# Joystick.net
KiCad netlist of a schematic drawn in Altium Designer
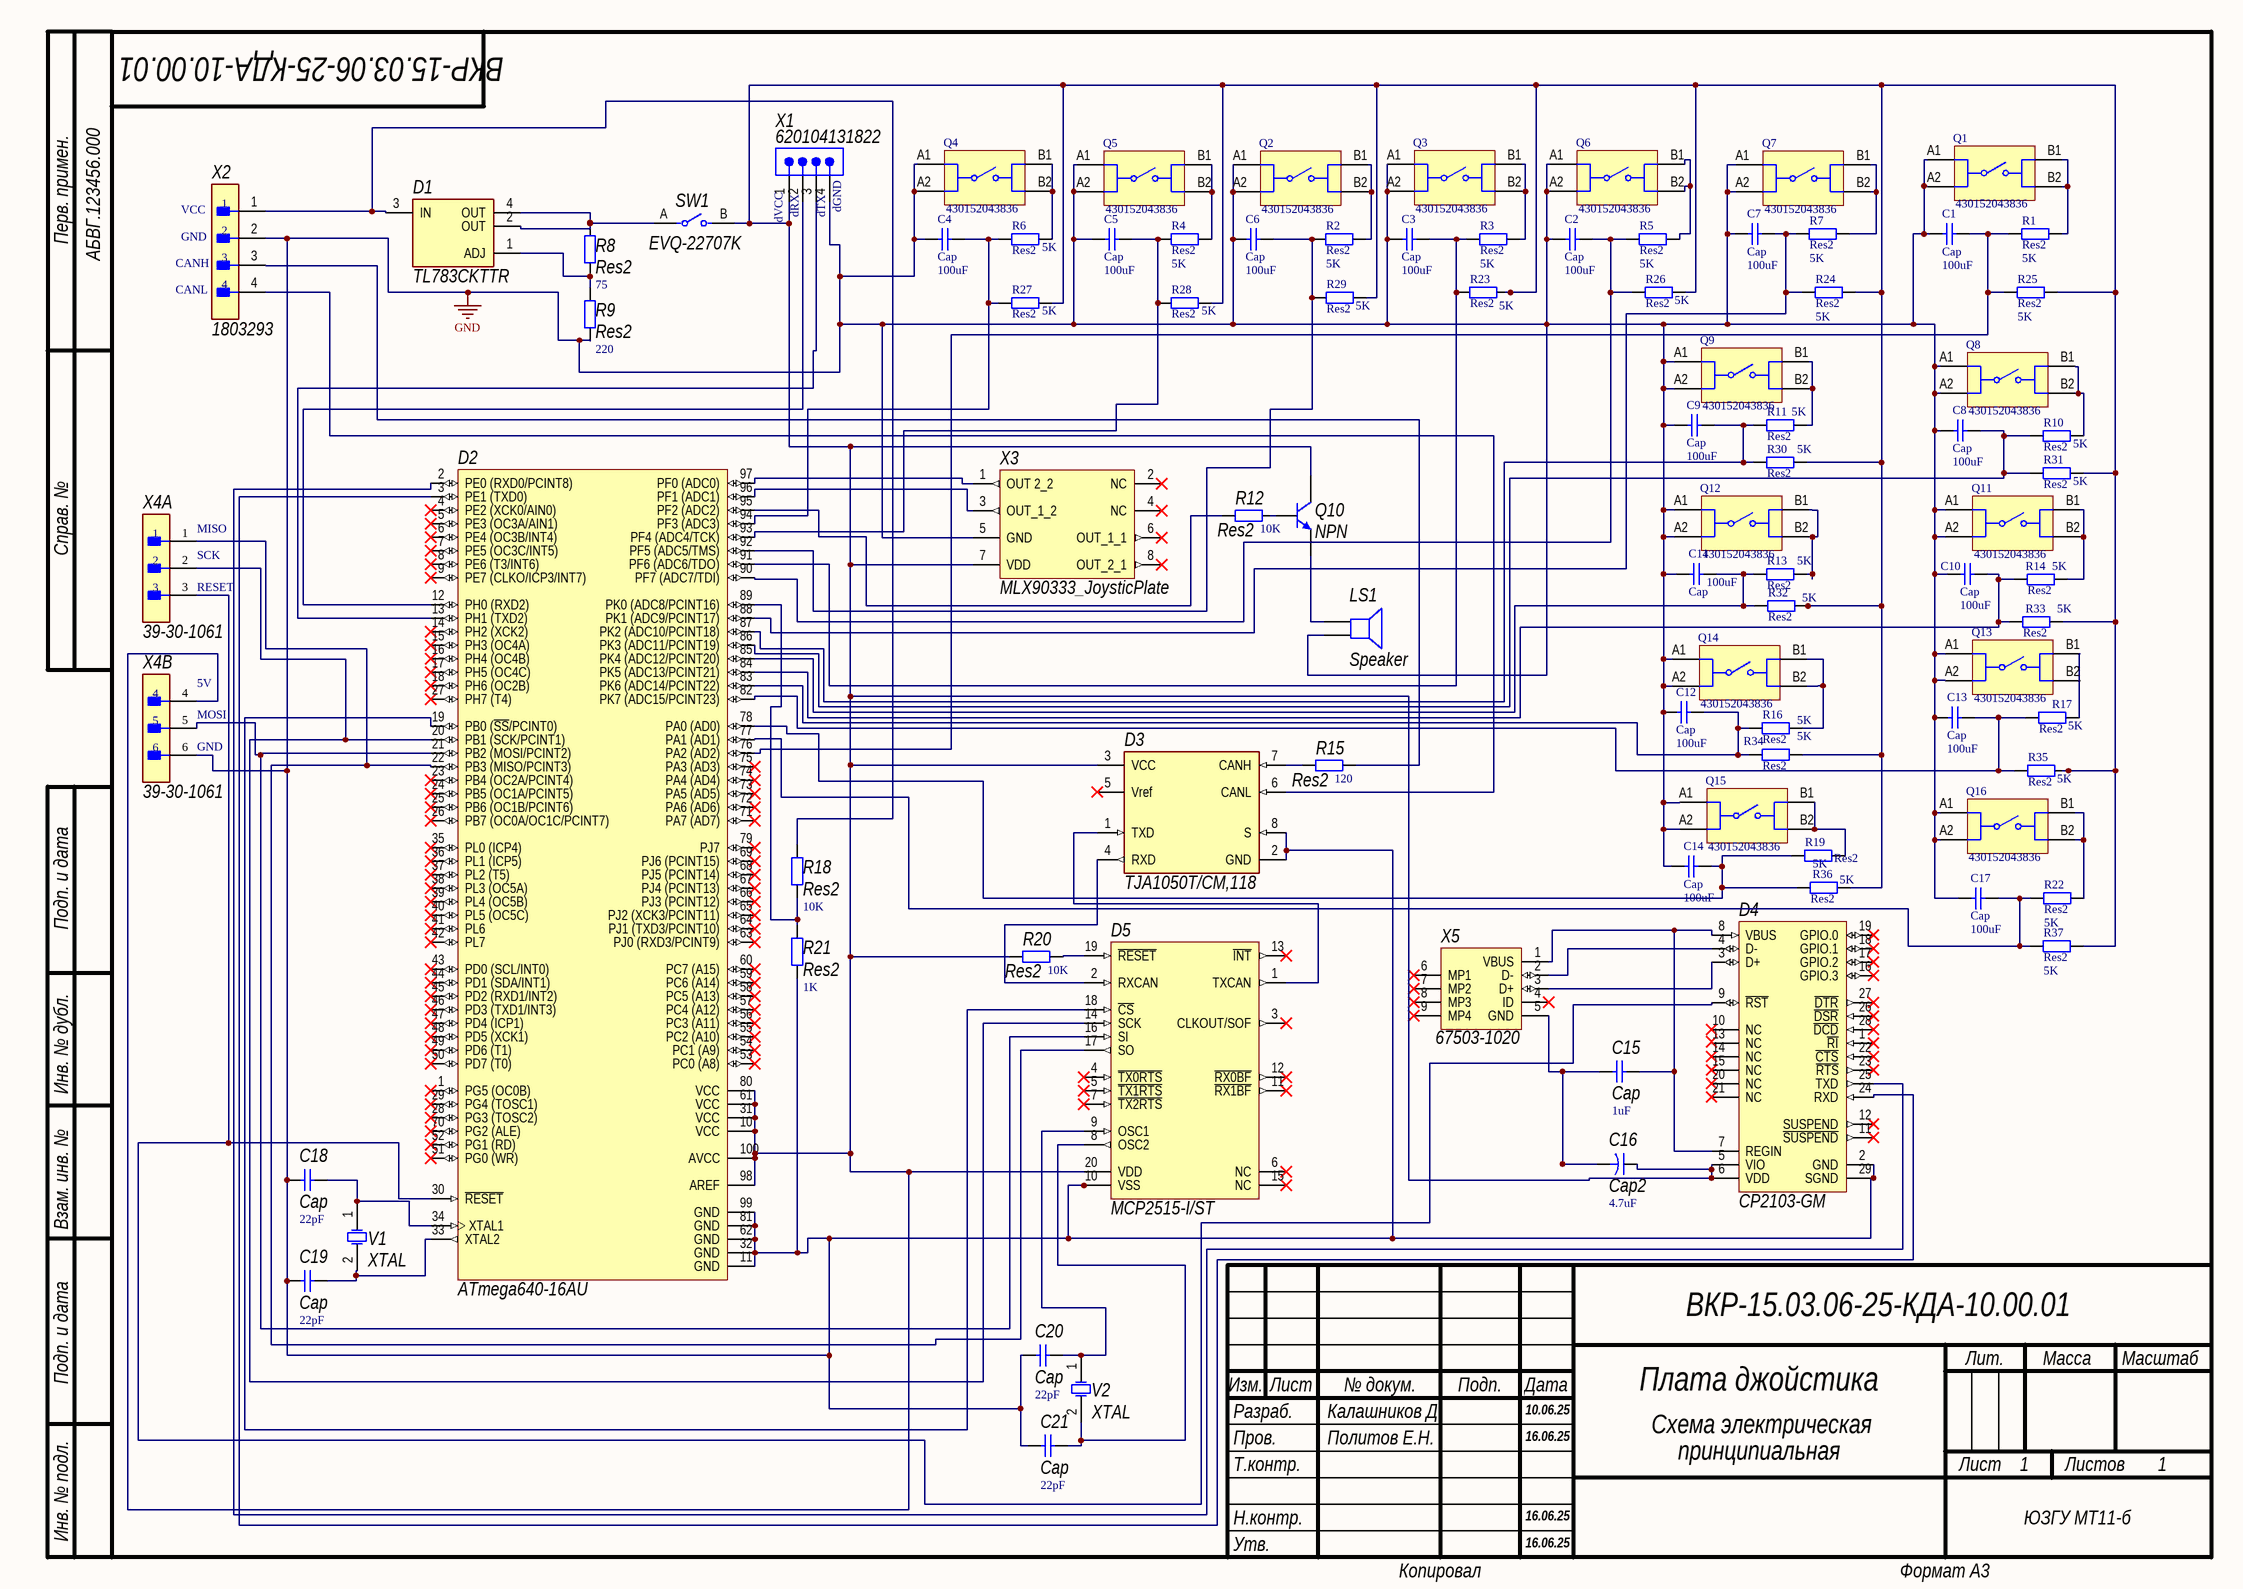
[diagram p0: Joystick.SchDoc]

(export (version "E")
  (design (tool "Eeschema 10.0.6"))
  (components
    (comp (ref "C1")
      (value "Cap")
      (footprint "RAD-0.3")
      (description "Capacitor")
      (fields (field (name "ALTIUM_VALUE") "100uF") (field (name "PUBLISHER") "Altium Limited"))
      (libsource (lib "Miscellaneous Devices") (part "Cap"))
    )
    (comp (ref "C2")
      (value "Cap")
      (footprint "RAD-0.3")
      (description "Capacitor")
      (fields (field (name "ALTIUM_VALUE") "100uF") (field (name "PUBLISHER") "Altium Limited"))
      (libsource (lib "Miscellaneous Devices") (part "Cap"))
    )
    (comp (ref "C3")
      (value "Cap")
      (footprint "RAD-0.3")
      (description "Capacitor")
      (fields (field (name "ALTIUM_VALUE") "100uF") (field (name "PUBLISHER") "Altium Limited"))
      (libsource (lib "Miscellaneous Devices") (part "Cap"))
    )
    (comp (ref "C4")
      (value "Cap")
      (footprint "RAD-0.3")
      (description "Capacitor")
      (fields (field (name "ALTIUM_VALUE") "100uF") (field (name "PUBLISHER") "Altium Limited"))
      (libsource (lib "Miscellaneous Devices") (part "Cap"))
    )
    (comp (ref "C5")
      (value "Cap")
      (footprint "RAD-0.3")
      (description "Capacitor")
      (fields (field (name "ALTIUM_VALUE") "100uF") (field (name "PUBLISHER") "Altium Limited"))
      (libsource (lib "Miscellaneous Devices") (part "Cap"))
    )
    (comp (ref "C6")
      (value "Cap")
      (footprint "RAD-0.3")
      (description "Capacitor")
      (fields (field (name "ALTIUM_VALUE") "100uF") (field (name "PUBLISHER") "Altium Limited"))
      (libsource (lib "Miscellaneous Devices") (part "Cap"))
    )
    (comp (ref "C7")
      (value "Cap")
      (footprint "RAD-0.3")
      (description "Capacitor")
      (fields (field (name "ALTIUM_VALUE") "100uF") (field (name "PUBLISHER") "Altium Limited"))
      (libsource (lib "Miscellaneous Devices") (part "Cap"))
    )
    (comp (ref "C8")
      (value "Cap")
      (footprint "RAD-0.3")
      (description "Capacitor")
      (fields (field (name "ALTIUM_VALUE") "100uF") (field (name "PUBLISHER") "Altium Limited"))
      (libsource (lib "Miscellaneous Devices") (part "Cap"))
    )
    (comp (ref "C9")
      (value "Cap")
      (footprint "RAD-0.3")
      (description "Capacitor")
      (fields (field (name "ALTIUM_VALUE") "100uF") (field (name "PUBLISHER") "Altium Limited"))
      (libsource (lib "Miscellaneous Devices") (part "Cap"))
    )
    (comp (ref "C10")
      (value "Cap")
      (footprint "RAD-0.3")
      (description "Capacitor")
      (fields (field (name "ALTIUM_VALUE") "100uF") (field (name "PUBLISHER") "Altium Limited"))
      (libsource (lib "Miscellaneous Devices") (part "Cap"))
    )
    (comp (ref "C11")
      (value "Cap")
      (footprint "RAD-0.3")
      (description "Capacitor")
      (fields (field (name "ALTIUM_VALUE") "100uF") (field (name "PUBLISHER") "Altium Limited"))
      (libsource (lib "Miscellaneous Devices") (part "Cap"))
    )
    (comp (ref "C12")
      (value "Cap")
      (footprint "RAD-0.3")
      (description "Capacitor")
      (fields (field (name "ALTIUM_VALUE") "100uF") (field (name "PUBLISHER") "Altium Limited"))
      (libsource (lib "Miscellaneous Devices") (part "Cap"))
    )
    (comp (ref "C13")
      (value "Cap")
      (footprint "RAD-0.3")
      (description "Capacitor")
      (fields (field (name "ALTIUM_VALUE") "100uF") (field (name "PUBLISHER") "Altium Limited"))
      (libsource (lib "Miscellaneous Devices") (part "Cap"))
    )
    (comp (ref "C14")
      (value "Cap")
      (footprint "RAD-0.3")
      (description "Capacitor")
      (fields (field (name "ALTIUM_VALUE") "100uF") (field (name "PUBLISHER") "Altium Limited"))
      (libsource (lib "Miscellaneous Devices") (part "Cap"))
    )
    (comp (ref "C15")
      (value "Cap")
      (footprint "RAD-0.3")
      (description "Capacitor")
      (fields (field (name "ALTIUM_VALUE") "1uF") (field (name "PUBLISHER") "Altium Limited"))
      (libsource (lib "Miscellaneous Devices") (part "Cap"))
    )
    (comp (ref "C16")
      (value "Cap2")
      (footprint "CAPR5-4X5")
      (description "Capacitor")
      (fields (field (name "ALTIUM_VALUE") "4.7uF") (field (name "PUBLISHER") "Altium Limited"))
      (libsource (lib "Miscellaneous Devices") (part "Cap2"))
    )
    (comp (ref "C17")
      (value "Cap")
      (footprint "RAD-0.3")
      (description "Capacitor")
      (fields (field (name "ALTIUM_VALUE") "100uF") (field (name "PUBLISHER") "Altium Limited"))
      (libsource (lib "Miscellaneous Devices") (part "Cap"))
    )
    (comp (ref "C18")
      (value "Cap")
      (footprint "RAD-0.3")
      (description "Capacitor")
      (fields (field (name "ALTIUM_VALUE") "22pF") (field (name "PUBLISHER") "Altium Limited"))
      (libsource (lib "Miscellaneous Devices") (part "Cap"))
    )
    (comp (ref "C19")
      (value "Cap")
      (footprint "RAD-0.3")
      (description "Capacitor")
      (fields (field (name "ALTIUM_VALUE") "22pF") (field (name "PUBLISHER") "Altium Limited"))
      (libsource (lib "Miscellaneous Devices") (part "Cap"))
    )
    (comp (ref "C20")
      (value "Cap")
      (footprint "RAD-0.3")
      (description "Capacitor")
      (fields (field (name "ALTIUM_VALUE") "22pF") (field (name "PUBLISHER") "Altium Limited"))
      (libsource (lib "Miscellaneous Devices") (part "Cap"))
    )
    (comp (ref "C21")
      (value "Cap")
      (footprint "RAD-0.3")
      (description "Capacitor")
      (fields (field (name "ALTIUM_VALUE") "22pF") (field (name "PUBLISHER") "Altium Limited"))
      (libsource (lib "Miscellaneous Devices") (part "Cap"))
    )
    (comp (ref "D1")
      (value "TL783CKTTR")
      (footprint "FP-KTT0003A-MFG")
      (description "IC REG LIN POS ADJ 700MA DDPAK")
      (libsource (lib "Altium Content Vault") (part "69b382e1026b3a4d462fbce2579e929"))
    )
    (comp (ref "D2")
      (value "ATmega640-16AU")
      (footprint "100A_M")
      (libsource (lib "Altium Content Vault") (part "MC-8B-ATM640-SQ100"))
    )
    (comp (ref "D3")
      (value "TJA1050T/CM,118")
      (footprint "FP-SOT96-1-IPC_A")
      (description "IC TRANSCEIVER HALF 1/1 8SO")
      (libsource (lib "Altium Content Vault") (part "cfdefafd38a55dc0607790f57b8a78f"))
    )
    (comp (ref "D4")
      (value "CP2103-GM")
      (footprint "SLAB-QFN-28-3125x3125TP_A_M")
      (description "Single-Chip USB to UART Bridge, 1024 Bytes EEPROM, -40 to 85 degC, 28-pin QFN, Tube")
      (fields (field (name "MANUFACTURER") "Silicon Labs"))
      (libsource (lib "Altium Content Vault") (part "SLAB-CP2103-QFN-28-29"))
    )
    (comp (ref "D5")
      (value "MCP2515-I/ST")
      (footprint "TSSOP-ST20_N")
      (description "Stand-Alone CAN Controller With SPI Interface, 20-Pin TSSOP, Industrial Temperature")
      (libsource (lib "Altium Content Vault") (part "COM-CAN-MCP2515-20"))
    )
    (comp (ref "LS1")
      (value "Speaker")
      (footprint "PIN2")
      (description "Loudspeaker")
      (fields (field (name "PUBLISHER") "Altium Limited"))
      (libsource (lib "Miscellaneous Devices") (part "Speaker"))
    )
    (comp (ref "Q1")
      (value "430152043836")
      (footprint "WS-TASV_L6W6H4.3_4301x20438x6")
      (libsource (lib "Altium Content Vault") (part "SPST-NO_4P"))
    )
    (comp (ref "Q2")
      (value "430152043836")
      (footprint "WS-TASV_L6W6H4.3_4301x20438x6")
      (libsource (lib "Altium Content Vault") (part "SPST-NO_4P"))
    )
    (comp (ref "Q3")
      (value "430152043836")
      (footprint "WS-TASV_L6W6H4.3_4301x20438x6")
      (libsource (lib "Altium Content Vault") (part "SPST-NO_4P"))
    )
    (comp (ref "Q4")
      (value "430152043836")
      (footprint "WS-TASV_L6W6H4.3_4301x20438x6")
      (libsource (lib "Altium Content Vault") (part "SPST-NO_4P"))
    )
    (comp (ref "Q5")
      (value "430152043836")
      (footprint "WS-TASV_L6W6H4.3_4301x20438x6")
      (libsource (lib "Altium Content Vault") (part "SPST-NO_4P"))
    )
    (comp (ref "Q6")
      (value "430152043836")
      (footprint "WS-TASV_L6W6H4.3_4301x20438x6")
      (libsource (lib "Altium Content Vault") (part "SPST-NO_4P"))
    )
    (comp (ref "Q7")
      (value "430152043836")
      (footprint "WS-TASV_L6W6H4.3_4301x20438x6")
      (libsource (lib "Altium Content Vault") (part "SPST-NO_4P"))
    )
    (comp (ref "Q8")
      (value "430152043836")
      (footprint "WS-TASV_L6W6H4.3_4301x20438x6")
      (libsource (lib "Altium Content Vault") (part "SPST-NO_4P"))
    )
    (comp (ref "Q9")
      (value "430152043836")
      (footprint "WS-TASV_L6W6H4.3_4301x20438x6")
      (libsource (lib "Altium Content Vault") (part "SPST-NO_4P"))
    )
    (comp (ref "Q10")
      (value "NPN")
      (footprint "TO-226-AA")
      (description "NPN Bipolar Transistor")
      (fields (field (name "PUBLISHER") "Altium Limited"))
      (libsource (lib "Miscellaneous Devices") (part "NPN"))
    )
    (comp (ref "Q11")
      (value "430152043836")
      (footprint "WS-TASV_L6W6H4.3_4301x20438x6")
      (libsource (lib "Altium Content Vault") (part "SPST-NO_4P"))
    )
    (comp (ref "Q12")
      (value "430152043836")
      (footprint "WS-TASV_L6W6H4.3_4301x20438x6")
      (libsource (lib "Altium Content Vault") (part "SPST-NO_4P"))
    )
    (comp (ref "Q13")
      (value "430152043836")
      (footprint "WS-TASV_L6W6H4.3_4301x20438x6")
      (libsource (lib "Altium Content Vault") (part "SPST-NO_4P"))
    )
    (comp (ref "Q14")
      (value "430152043836")
      (footprint "WS-TASV_L6W6H4.3_4301x20438x6")
      (libsource (lib "Altium Content Vault") (part "SPST-NO_4P"))
    )
    (comp (ref "Q15")
      (value "430152043836")
      (footprint "WS-TASV_L6W6H4.3_4301x20438x6")
      (libsource (lib "Altium Content Vault") (part "SPST-NO_4P"))
    )
    (comp (ref "Q16")
      (value "430152043836")
      (footprint "WS-TASV_L6W6H4.3_4301x20438x6")
      (libsource (lib "Altium Content Vault") (part "SPST-NO_4P"))
    )
    (comp (ref "R1")
      (value "Res2")
      (footprint "AXIAL-0.4")
      (description "Resistor")
      (fields (field (name "ALTIUM_VALUE") "5K") (field (name "PUBLISHER") "Altium Limited"))
      (libsource (lib "Miscellaneous Devices") (part "Res2"))
    )
    (comp (ref "R2")
      (value "Res2")
      (footprint "AXIAL-0.4")
      (description "Resistor")
      (fields (field (name "ALTIUM_VALUE") "5K") (field (name "PUBLISHER") "Altium Limited"))
      (libsource (lib "Miscellaneous Devices") (part "Res2"))
    )
    (comp (ref "R3")
      (value "Res2")
      (footprint "AXIAL-0.4")
      (description "Resistor")
      (fields (field (name "ALTIUM_VALUE") "5K") (field (name "PUBLISHER") "Altium Limited"))
      (libsource (lib "Miscellaneous Devices") (part "Res2"))
    )
    (comp (ref "R4")
      (value "Res2")
      (footprint "AXIAL-0.4")
      (description "Resistor")
      (fields (field (name "ALTIUM_VALUE") "5K") (field (name "PUBLISHER") "Altium Limited"))
      (libsource (lib "Miscellaneous Devices") (part "Res2"))
    )
    (comp (ref "R5")
      (value "Res2")
      (footprint "AXIAL-0.4")
      (description "Resistor")
      (fields (field (name "ALTIUM_VALUE") "5K") (field (name "PUBLISHER") "Altium Limited"))
      (libsource (lib "Miscellaneous Devices") (part "Res2"))
    )
    (comp (ref "R6")
      (value "Res2")
      (footprint "AXIAL-0.4")
      (description "Resistor")
      (fields (field (name "ALTIUM_VALUE") "5K") (field (name "PUBLISHER") "Altium Limited"))
      (libsource (lib "Miscellaneous Devices") (part "Res2"))
    )
    (comp (ref "R7")
      (value "Res2")
      (footprint "AXIAL-0.4")
      (description "Resistor")
      (fields (field (name "ALTIUM_VALUE") "5K") (field (name "PUBLISHER") "Altium Limited"))
      (libsource (lib "Miscellaneous Devices") (part "Res2"))
    )
    (comp (ref "R8")
      (value "Res2")
      (footprint "AXIAL-0.4")
      (description "Resistor")
      (fields (field (name "ALTIUM_VALUE") "75") (field (name "PUBLISHER") "Altium Limited"))
      (libsource (lib "") (part "Res2_2"))
    )
    (comp (ref "R9")
      (value "Res2")
      (footprint "AXIAL-0.4")
      (description "Resistor")
      (fields (field (name "ALTIUM_VALUE") "220") (field (name "PUBLISHER") "Altium Limited"))
      (libsource (lib "") (part "Res2_2"))
    )
    (comp (ref "R10")
      (value "Res2")
      (footprint "AXIAL-0.4")
      (description "Resistor")
      (fields (field (name "ALTIUM_VALUE") "5K") (field (name "PUBLISHER") "Altium Limited"))
      (libsource (lib "Miscellaneous Devices") (part "Res2"))
    )
    (comp (ref "R11")
      (value "Res2")
      (footprint "AXIAL-0.4")
      (description "Resistor")
      (fields (field (name "ALTIUM_VALUE") "5K") (field (name "PUBLISHER") "Altium Limited"))
      (libsource (lib "Miscellaneous Devices") (part "Res2"))
    )
    (comp (ref "R12")
      (value "Res2")
      (footprint "AXIAL-0.4")
      (description "Resistor")
      (fields (field (name "ALTIUM_VALUE") "10K") (field (name "PUBLISHER") "Altium Limited"))
      (libsource (lib "") (part "Res2_1"))
    )
    (comp (ref "R13")
      (value "Res2")
      (footprint "AXIAL-0.4")
      (description "Resistor")
      (fields (field (name "ALTIUM_VALUE") "5K") (field (name "PUBLISHER") "Altium Limited"))
      (libsource (lib "") (part "Res2_1"))
    )
    (comp (ref "R14")
      (value "Res2")
      (footprint "AXIAL-0.4")
      (description "Resistor")
      (fields (field (name "ALTIUM_VALUE") "5K") (field (name "PUBLISHER") "Altium Limited"))
      (libsource (lib "") (part "Res2_1"))
    )
    (comp (ref "R15")
      (value "Res2")
      (footprint "AXIAL-0.4")
      (description "Resistor")
      (fields (field (name "ALTIUM_VALUE") "120") (field (name "PUBLISHER") "Altium Limited"))
      (libsource (lib "") (part "Res2_1"))
    )
    (comp (ref "R16")
      (value "Res2")
      (footprint "AXIAL-0.4")
      (description "Resistor")
      (fields (field (name "ALTIUM_VALUE") "5K") (field (name "PUBLISHER") "Altium Limited"))
      (libsource (lib "Miscellaneous Devices") (part "Res2"))
    )
    (comp (ref "R17")
      (value "Res2")
      (footprint "AXIAL-0.4")
      (description "Resistor")
      (fields (field (name "ALTIUM_VALUE") "5K") (field (name "PUBLISHER") "Altium Limited"))
      (libsource (lib "Miscellaneous Devices") (part "Res2"))
    )
    (comp (ref "R18")
      (value "Res2")
      (footprint "AXIAL-0.4")
      (description "Resistor")
      (fields (field (name "ALTIUM_VALUE") "10K") (field (name "PUBLISHER") "Altium Limited"))
      (libsource (lib "") (part "Res2_3"))
    )
    (comp (ref "R19")
      (value "Res2")
      (footprint "AXIAL-0.4")
      (description "Resistor")
      (fields (field (name "ALTIUM_VALUE") "5K") (field (name "PUBLISHER") "Altium Limited"))
      (libsource (lib "") (part "Res2_1"))
    )
    (comp (ref "R20")
      (value "Res2")
      (footprint "AXIAL-0.4")
      (description "Resistor")
      (fields (field (name "ALTIUM_VALUE") "10K") (field (name "PUBLISHER") "Altium Limited"))
      (libsource (lib "") (part "Res2_1"))
    )
    (comp (ref "R21")
      (value "Res2")
      (footprint "AXIAL-0.4")
      (description "Resistor")
      (fields (field (name "ALTIUM_VALUE") "1K") (field (name "PUBLISHER") "Altium Limited"))
      (libsource (lib "") (part "Res2_3"))
    )
    (comp (ref "R22")
      (value "Res2")
      (footprint "AXIAL-0.4")
      (description "Resistor")
      (fields (field (name "ALTIUM_VALUE") "5K") (field (name "PUBLISHER") "Altium Limited"))
      (libsource (lib "") (part "Res2_1"))
    )
    (comp (ref "R23")
      (value "Res2")
      (footprint "AXIAL-0.4")
      (description "Resistor")
      (fields (field (name "ALTIUM_VALUE") "5K") (field (name "PUBLISHER") "Altium Limited"))
      (libsource (lib "Miscellaneous Devices") (part "Res2"))
    )
    (comp (ref "R24")
      (value "Res2")
      (footprint "AXIAL-0.4")
      (description "Resistor")
      (fields (field (name "ALTIUM_VALUE") "5K") (field (name "PUBLISHER") "Altium Limited"))
      (libsource (lib "Miscellaneous Devices") (part "Res2"))
    )
    (comp (ref "R25")
      (value "Res2")
      (footprint "AXIAL-0.4")
      (description "Resistor")
      (fields (field (name "ALTIUM_VALUE") "5K") (field (name "PUBLISHER") "Altium Limited"))
      (libsource (lib "Miscellaneous Devices") (part "Res2"))
    )
    (comp (ref "R26")
      (value "Res2")
      (footprint "AXIAL-0.4")
      (description "Resistor")
      (fields (field (name "ALTIUM_VALUE") "5K") (field (name "PUBLISHER") "Altium Limited"))
      (libsource (lib "Miscellaneous Devices") (part "Res2"))
    )
    (comp (ref "R27")
      (value "Res2")
      (footprint "AXIAL-0.4")
      (description "Resistor")
      (fields (field (name "ALTIUM_VALUE") "5K") (field (name "PUBLISHER") "Altium Limited"))
      (libsource (lib "Miscellaneous Devices") (part "Res2"))
    )
    (comp (ref "R28")
      (value "Res2")
      (footprint "AXIAL-0.4")
      (description "Resistor")
      (fields (field (name "ALTIUM_VALUE") "5K") (field (name "PUBLISHER") "Altium Limited"))
      (libsource (lib "Miscellaneous Devices") (part "Res2"))
    )
    (comp (ref "R29")
      (value "Res2")
      (footprint "AXIAL-0.4")
      (description "Resistor")
      (fields (field (name "ALTIUM_VALUE") "5K") (field (name "PUBLISHER") "Altium Limited"))
      (libsource (lib "Miscellaneous Devices") (part "Res2"))
    )
    (comp (ref "R30")
      (value "Res2")
      (footprint "AXIAL-0.4")
      (description "Resistor")
      (fields (field (name "ALTIUM_VALUE") "5K") (field (name "PUBLISHER") "Altium Limited"))
      (libsource (lib "Miscellaneous Devices") (part "Res2"))
    )
    (comp (ref "R31")
      (value "Res2")
      (footprint "AXIAL-0.4")
      (description "Resistor")
      (fields (field (name "ALTIUM_VALUE") "5K") (field (name "PUBLISHER") "Altium Limited"))
      (libsource (lib "Miscellaneous Devices") (part "Res2"))
    )
    (comp (ref "R32")
      (value "Res2")
      (footprint "AXIAL-0.4")
      (description "Resistor")
      (fields (field (name "ALTIUM_VALUE") "5K") (field (name "PUBLISHER") "Altium Limited"))
      (libsource (lib "") (part "Res2_1"))
    )
    (comp (ref "R33")
      (value "Res2")
      (footprint "AXIAL-0.4")
      (description "Resistor")
      (fields (field (name "ALTIUM_VALUE") "5K") (field (name "PUBLISHER") "Altium Limited"))
      (libsource (lib "") (part "Res2_1"))
    )
    (comp (ref "R34")
      (value "Res2")
      (footprint "AXIAL-0.4")
      (description "Resistor")
      (fields (field (name "ALTIUM_VALUE") "5K") (field (name "PUBLISHER") "Altium Limited"))
      (libsource (lib "Miscellaneous Devices") (part "Res2"))
    )
    (comp (ref "R35")
      (value "Res2")
      (footprint "AXIAL-0.4")
      (description "Resistor")
      (fields (field (name "ALTIUM_VALUE") "5K") (field (name "PUBLISHER") "Altium Limited"))
      (libsource (lib "Miscellaneous Devices") (part "Res2"))
    )
    (comp (ref "R36")
      (value "Res2")
      (footprint "AXIAL-0.4")
      (description "Resistor")
      (fields (field (name "ALTIUM_VALUE") "5K") (field (name "PUBLISHER") "Altium Limited"))
      (libsource (lib "") (part "Res2_1"))
    )
    (comp (ref "R37")
      (value "Res2")
      (footprint "AXIAL-0.4")
      (description "Resistor")
      (fields (field (name "ALTIUM_VALUE") "5K") (field (name "PUBLISHER") "Altium Limited"))
      (libsource (lib "") (part "Res2_1"))
    )
    (comp (ref "SW1")
      (value "EVQ-22707K")
      (footprint "FP-EVQ-22707K-MFG")
      (description "SWITCH TACTILE SPST-NO 0.02A 15V")
      (libsource (lib "Altium Content Vault") (part "2b0b2b19372efd94fa7681498149756"))
    )
    (comp (ref "V1")
      (value "XTAL")
      (footprint "R38")
      (description "Crystal Oscillator")
      (fields (field (name "PUBLISHER") "Altium Limited"))
      (libsource (lib "Miscellaneous Devices") (part "XTAL"))
    )
    (comp (ref "V2")
      (value "XTAL")
      (footprint "R38")
      (description "Crystal Oscillator")
      (fields (field (name "PUBLISHER") "Altium Limited"))
      (libsource (lib "Miscellaneous Devices") (part "XTAL"))
    )
    (comp (ref "X1")
      (value "620104131822")
      (footprint "620104131822")
      (libsource (lib "Altium Content Vault") (part "Header_Male_1R_04P"))
    )
    (comp (ref "X2")
      (value "1803293")
      (footprint "FP-1803293-MFG")
      (description "TERM BLOCK HDR 4POS 90DEG 3.81MM")
      (fields (field (name "VOLTAGE") "300V"))
      (libsource (lib "Altium Content Vault") (part "299a8cea1bdcbc3624fe62c390fa72c"))
    )
    (comp (ref "X3")
      (value "MLX90333_JoysticPlate")
      (footprint "MLX90333_Joy")
      (libsource (lib "Joystiks") (part "MLX90333_JoysticPlate"))
    )
    (comp (ref "X4")
      (value "39-30-1061")
      (footprint "FP-39-30-1061-MFG")
      (description "39-30-1061 Connector Wire to Board Header 6 Position 4.2mm Solder Right Angle Thru-Hole Tray")
      (libsource (lib "Altium Content Vault") (part "7bb5f7ddfb2bec276e641070710345c"))
    )
    (comp (ref "X5")
      (value "67503-1020")
      (footprint "MOLX-67503-1020_V")
      (description "USB, MINI, SMD, RA KME04-USBMU03A01")
      (fields (field (name "MANUFACTURER") "Molex"))
      (libsource (lib "Altium Content Vault") (part "MOLX-67503-1020"))
    )
  )
  (nets
    (net (code "1") (name "GND") (class "Default")
      (node (ref "C1") (pin "1") (pinfunction "1_1") (pintype "passive"))
      (node (ref "C10") (pin "2") (pinfunction "2_2") (pintype "passive"))
      (node (ref "C11") (pin "1") (pinfunction "1_1") (pintype "passive"))
      (node (ref "C12") (pin "1") (pinfunction "1_1") (pintype "passive"))
      (node (ref "C13") (pin "1") (pinfunction "1_1") (pintype "passive"))
      (node (ref "C14") (pin "1") (pinfunction "1_1") (pintype "passive"))
      (node (ref "C17") (pin "1") (pinfunction "1_1") (pintype "passive"))
      (node (ref "C18") (pin "2") (pinfunction "2_2") (pintype "passive"))
      (node (ref "C19") (pin "1") (pinfunction "1_1") (pintype "passive"))
      (node (ref "C2") (pin "1") (pinfunction "1_1") (pintype "passive"))
      (node (ref "C20") (pin "1") (pinfunction "1_1") (pintype "passive"))
      (node (ref "C21") (pin "1") (pinfunction "1_1") (pintype "passive"))
      (node (ref "C3") (pin "1") (pinfunction "1_1") (pintype "passive"))
      (node (ref "C4") (pin "1") (pinfunction "1_1") (pintype "passive"))
      (node (ref "C5") (pin "1") (pinfunction "1_1") (pintype "passive"))
      (node (ref "C6") (pin "1") (pinfunction "1_1") (pintype "passive"))
      (node (ref "C7") (pin "1") (pinfunction "1_1") (pintype "passive"))
      (node (ref "C8") (pin "1") (pinfunction "1_1") (pintype "passive"))
      (node (ref "C9") (pin "2") (pinfunction "2_2") (pintype "passive"))
      (node (ref "D2") (pin "11") (pinfunction "GND_11") (pintype "power_in"))
      (node (ref "D2") (pin "32") (pinfunction "GND_32") (pintype "power_in"))
      (node (ref "D2") (pin "62") (pinfunction "GND_62") (pintype "power_in"))
      (node (ref "D2") (pin "81") (pinfunction "GND_81") (pintype "power_in"))
      (node (ref "D2") (pin "99") (pinfunction "GND_99") (pintype "power_in"))
      (node (ref "D3") (pin "2") (pinfunction "GND_2") (pintype "power_in"))
      (node (ref "D3") (pin "8") (pinfunction "S_8") (pintype "input"))
      (node (ref "D4") (pin "2") (pinfunction "GND_2") (pintype "power_in"))
      (node (ref "D4") (pin "29") (pinfunction "SGND_29") (pintype "power_in"))
      (node (ref "D5") (pin "10") (pinfunction "VSS_10") (pintype "power_in"))
      (node (ref "LS1") (pin "2") (pinfunction "2_2") (pintype "passive"))
      (node (ref "Q1") (pin "A1") (pinfunction "A1_A1") (pintype "passive"))
      (node (ref "Q1") (pin "A2") (pinfunction "A2_A2") (pintype "passive"))
      (node (ref "Q11") (pin "A1") (pinfunction "A1_A1") (pintype "passive"))
      (node (ref "Q11") (pin "A2") (pinfunction "A2_A2") (pintype "passive"))
      (node (ref "Q12") (pin "A1") (pinfunction "A1_A1") (pintype "passive"))
      (node (ref "Q12") (pin "A2") (pinfunction "A2_A2") (pintype "passive"))
      (node (ref "Q13") (pin "A1") (pinfunction "A1_A1") (pintype "passive"))
      (node (ref "Q13") (pin "A2") (pinfunction "A2_A2") (pintype "passive"))
      (node (ref "Q14") (pin "A1") (pinfunction "A1_A1") (pintype "passive"))
      (node (ref "Q14") (pin "A2") (pinfunction "A2_A2") (pintype "passive"))
      (node (ref "Q15") (pin "A1") (pinfunction "A1_A1") (pintype "passive"))
      (node (ref "Q15") (pin "A2") (pinfunction "A2_A2") (pintype "passive"))
      (node (ref "Q16") (pin "A1") (pinfunction "A1_A1") (pintype "passive"))
      (node (ref "Q16") (pin "A2") (pinfunction "A2_A2") (pintype "passive"))
      (node (ref "Q2") (pin "A1") (pinfunction "A1_A1") (pintype "passive"))
      (node (ref "Q2") (pin "A2") (pinfunction "A2_A2") (pintype "passive"))
      (node (ref "Q3") (pin "A1") (pinfunction "A1_A1") (pintype "passive"))
      (node (ref "Q3") (pin "A2") (pinfunction "A2_A2") (pintype "passive"))
      (node (ref "Q4") (pin "A1") (pinfunction "A1_A1") (pintype "passive"))
      (node (ref "Q4") (pin "A2") (pinfunction "A2_A2") (pintype "passive"))
      (node (ref "Q5") (pin "A1") (pinfunction "A1_A1") (pintype "passive"))
      (node (ref "Q5") (pin "A2") (pinfunction "A2_A2") (pintype "passive"))
      (node (ref "Q6") (pin "A1") (pinfunction "A1_A1") (pintype "passive"))
      (node (ref "Q6") (pin "A2") (pinfunction "A2_A2") (pintype "passive"))
      (node (ref "Q7") (pin "A1") (pinfunction "A1_A1") (pintype "passive"))
      (node (ref "Q7") (pin "A2") (pinfunction "A2_A2") (pintype "passive"))
      (node (ref "Q8") (pin "A1") (pinfunction "A1_A1") (pintype "passive"))
      (node (ref "Q8") (pin "A2") (pinfunction "A2_A2") (pintype "passive"))
      (node (ref "Q9") (pin "A1") (pinfunction "A1_A1") (pintype "passive"))
      (node (ref "Q9") (pin "A2") (pinfunction "A2_A2") (pintype "passive"))
      (node (ref "R21") (pin "1") (pinfunction "1_1") (pintype "passive"))
      (node (ref "R9") (pin "2") (pinfunction "2_2") (pintype "passive"))
      (node (ref "X1") (pin "4") (pinfunction "4_4") (pintype "passive"))
      (node (ref "X2") (pin "2") (pinfunction "2_2") (pintype "passive"))
      (node (ref "X3") (pin "5") (pinfunction "GND_5") (pintype "power_in"))
      (node (ref "X4") (pin "6") (pinfunction "6_6") (pintype "passive"))
    )
    (net (code "2") (name "Net-(D1-ADJ)") (class "Default")
      (node (ref "D1") (pin "1") (pinfunction "ADJ_1") (pintype "passive"))
      (node (ref "R8") (pin "2") (pinfunction "2_2") (pintype "passive"))
      (node (ref "R9") (pin "1") (pinfunction "1_1") (pintype "passive"))
    )
    (net (code "3") (name "Net-(D1-IN)") (class "Default")
      (node (ref "D1") (pin "3") (pinfunction "IN_3") (pintype "power_in"))
      (node (ref "R18") (pin "2") (pinfunction "2_2") (pintype "passive"))
      (node (ref "X2") (pin "1") (pinfunction "1_1") (pintype "passive"))
    )
    (net (code "4") (name "Net-(D1-OUT-Pad2)") (class "Default")
      (node (ref "D1") (pin "2") (pinfunction "OUT_2") (pintype "power_in"))
      (node (ref "D1") (pin "4") (pinfunction "OUT_4") (pintype "power_in"))
      (node (ref "R8") (pin "1") (pinfunction "1_1") (pintype "passive"))
      (node (ref "SW1") (pin "A") (pinfunction "A_A") (pintype "passive"))
    )
    (net (code "5") (name "Net-(D2-AREF)") (class "Default")
      (node (ref "C16") (pin "1") (pinfunction "1_1") (pintype "passive"))
      (node (ref "D2") (pin "10") (pinfunction "VCC_10") (pintype "power_in"))
      (node (ref "D2") (pin "100") (pinfunction "AVCC_100") (pintype "power_in"))
      (node (ref "D2") (pin "31") (pinfunction "VCC_31") (pintype "power_in"))
      (node (ref "D2") (pin "61") (pinfunction "VCC_61") (pintype "power_in"))
      (node (ref "D2") (pin "80") (pinfunction "VCC_80") (pintype "power_in"))
      (node (ref "D2") (pin "98") (pinfunction "AREF_98") (pintype "power_in"))
      (node (ref "D3") (pin "3") (pinfunction "VCC_3") (pintype "power_in"))
      (node (ref "D4") (pin "5") (pinfunction "VIO_5") (pintype "power_in"))
      (node (ref "D4") (pin "6") (pinfunction "VDD_6") (pintype "power_in"))
      (node (ref "D5") (pin "20") (pinfunction "VDD_20") (pintype "power_in"))
      (node (ref "Q10") (pin "1") (pinfunction "C_1") (pintype "passive"))
      (node (ref "R20") (pin "1") (pinfunction "1_1") (pintype "passive"))
      (node (ref "R23") (pin "1") (pinfunction "1_1") (pintype "passive"))
      (node (ref "R24") (pin "1") (pinfunction "1_1") (pintype "passive"))
      (node (ref "R25") (pin "1") (pinfunction "1_1") (pintype "passive"))
      (node (ref "R26") (pin "1") (pinfunction "1_1") (pintype "passive"))
      (node (ref "R27") (pin "1") (pinfunction "1_1") (pintype "passive"))
      (node (ref "R28") (pin "1") (pinfunction "1_1") (pintype "passive"))
      (node (ref "R29") (pin "1") (pinfunction "1_1") (pintype "passive"))
      (node (ref "R30") (pin "1") (pinfunction "1_1") (pintype "passive"))
      (node (ref "R31") (pin "1") (pinfunction "1_1") (pintype "passive"))
      (node (ref "R32") (pin "2") (pinfunction "2_2") (pintype "passive"))
      (node (ref "R33") (pin "2") (pinfunction "2_2") (pintype "passive"))
      (node (ref "R34") (pin "1") (pinfunction "1_1") (pintype "passive"))
      (node (ref "R35") (pin "1") (pinfunction "1_1") (pintype "passive"))
      (node (ref "R36") (pin "2") (pinfunction "2_2") (pintype "passive"))
      (node (ref "R37") (pin "2") (pinfunction "2_2") (pintype "passive"))
      (node (ref "SW1") (pin "B") (pinfunction "B_B") (pintype "passive"))
      (node (ref "X1") (pin "1") (pinfunction "1_1") (pintype "passive"))
      (node (ref "X3") (pin "7") (pinfunction "VDD_7") (pintype "power_in"))
      (node (ref "X4") (pin "4") (pinfunction "4_4") (pintype "passive"))
    )
    (net (code "6") (name "Net-(D2-PA0_(AD0))") (class "Default")
      (node (ref "C14") (pin "2") (pinfunction "2_2") (pintype "passive"))
      (node (ref "D2") (pin "78") (pinfunction "PA0_(AD0)_78") (pintype "bidirectional"))
      (node (ref "R19") (pin "1") (pinfunction "1_1") (pintype "passive"))
      (node (ref "R36") (pin "1") (pinfunction "1_1") (pintype "passive"))
    )
    (net (code "7") (name "Net-(D2-PA1_(AD1))") (class "Default")
      (node (ref "C17") (pin "2") (pinfunction "2_2") (pintype "passive"))
      (node (ref "D2") (pin "77") (pinfunction "PA1_(AD1)_77") (pintype "bidirectional"))
      (node (ref "R22") (pin "1") (pinfunction "1_1") (pintype "passive"))
      (node (ref "R37") (pin "1") (pinfunction "1_1") (pintype "passive"))
    )
    (net (code "8") (name "Net-(D2-PA2_(AD2))") (class "Default")
      (node (ref "C1") (pin "2") (pinfunction "2_2") (pintype "passive"))
      (node (ref "D2") (pin "76") (pinfunction "PA2_(AD2)_76") (pintype "bidirectional"))
      (node (ref "R1") (pin "2") (pinfunction "2_2") (pintype "passive"))
      (node (ref "R25") (pin "2") (pinfunction "2_2") (pintype "passive"))
    )
    (net (code "9") (name "Net-(D2-PB0_(~{SS}{slash}PCINT0))") (class "Default")
      (node (ref "D2") (pin "19") (pinfunction "PB0_(~{SS}/PCINT0)_19") (pintype "bidirectional"))
      (node (ref "D5") (pin "18") (pinfunction "~{CS}_18") (pintype "input"))
    )
    (net (code "10") (name "Net-(D2-PB1_(SCK{slash}PCINT1))") (class "Default")
      (node (ref "D2") (pin "20") (pinfunction "PB1_(SCK/PCINT1)_20") (pintype "bidirectional"))
      (node (ref "D5") (pin "14") (pinfunction "SCK_14") (pintype "input"))
      (node (ref "X4") (pin "2") (pinfunction "2_2") (pintype "passive"))
    )
    (net (code "11") (name "Net-(D2-PB2_(MOSI{slash}PCINT2))") (class "Default")
      (node (ref "D2") (pin "21") (pinfunction "PB2_(MOSI/PCINT2)_21") (pintype "bidirectional"))
      (node (ref "D5") (pin "16") (pinfunction "SI_16") (pintype "input"))
      (node (ref "X4") (pin "5") (pinfunction "5_5") (pintype "passive"))
    )
    (net (code "12") (name "Net-(D2-PB3_(MISO{slash}PCINT3))") (class "Default")
      (node (ref "D2") (pin "22") (pinfunction "PB3_(MISO/PCINT3)_22") (pintype "bidirectional"))
      (node (ref "D5") (pin "17") (pinfunction "SO_17") (pintype "output"))
      (node (ref "X4") (pin "1") (pinfunction "1_1") (pintype "passive"))
    )
    (net (code "13") (name "Net-(D2-PE0_(RXD0{slash}PCINT8))") (class "Default")
      (node (ref "D2") (pin "2") (pinfunction "PE0_(RXD0/PCINT8)_2") (pintype "bidirectional"))
      (node (ref "D4") (pin "25") (pinfunction "TXD_25") (pintype "output"))
    )
    (net (code "14") (name "Net-(D2-PE1_(TXD0))") (class "Default")
      (node (ref "D2") (pin "3") (pinfunction "PE1_(TXD0)_3") (pintype "bidirectional"))
      (node (ref "D4") (pin "24") (pinfunction "RXD_24") (pintype "input"))
    )
    (net (code "15") (name "Net-(D2-PF0_(ADC0))") (class "Default")
      (node (ref "D2") (pin "97") (pinfunction "PF0_(ADC0)_97") (pintype "bidirectional"))
      (node (ref "X3") (pin "1") (pinfunction "OUT_2_2_1") (pintype "output"))
    )
    (net (code "16") (name "Net-(D2-PF1_(ADC1))") (class "Default")
      (node (ref "D2") (pin "96") (pinfunction "PF1_(ADC1)_96") (pintype "bidirectional"))
      (node (ref "X3") (pin "3") (pinfunction "OUT_1_2_3") (pintype "output"))
    )
    (net (code "17") (name "Net-(D2-PF2_(ADC2))") (class "Default")
      (node (ref "D2") (pin "95") (pinfunction "PF2_(ADC2)_95") (pintype "bidirectional"))
      (node (ref "R12") (pin "1") (pinfunction "1_1") (pintype "passive"))
    )
    (net (code "18") (name "Net-(D2-PF3_(ADC3))") (class "Default")
      (node (ref "C4") (pin "2") (pinfunction "2_2") (pintype "passive"))
      (node (ref "D2") (pin "94") (pinfunction "PF3_(ADC3)_94") (pintype "bidirectional"))
      (node (ref "R27") (pin "2") (pinfunction "2_2") (pintype "passive"))
      (node (ref "R6") (pin "2") (pinfunction "2_2") (pintype "passive"))
    )
    (net (code "19") (name "Net-(D2-PF4_(ADC4{slash}TCK))") (class "Default")
      (node (ref "C5") (pin "2") (pinfunction "2_2") (pintype "passive"))
      (node (ref "D2") (pin "93") (pinfunction "PF4_(ADC4/TCK)_93") (pintype "bidirectional"))
      (node (ref "R28") (pin "2") (pinfunction "2_2") (pintype "passive"))
      (node (ref "R4") (pin "2") (pinfunction "2_2") (pintype "passive"))
    )
    (net (code "20") (name "Net-(D2-PF5_(ADC5{slash}TMS))") (class "Default")
      (node (ref "C6") (pin "2") (pinfunction "2_2") (pintype "passive"))
      (node (ref "D2") (pin "92") (pinfunction "PF5_(ADC5/TMS)_92") (pintype "bidirectional"))
      (node (ref "R2") (pin "2") (pinfunction "2_2") (pintype "passive"))
      (node (ref "R29") (pin "2") (pinfunction "2_2") (pintype "passive"))
    )
    (net (code "21") (name "Net-(D2-PF6_(ADC6{slash}TDO))") (class "Default")
      (node (ref "C3") (pin "2") (pinfunction "2_2") (pintype "passive"))
      (node (ref "D2") (pin "91") (pinfunction "PF6_(ADC6/TDO)_91") (pintype "bidirectional"))
      (node (ref "R23") (pin "2") (pinfunction "2_2") (pintype "passive"))
      (node (ref "R3") (pin "2") (pinfunction "2_2") (pintype "passive"))
    )
    (net (code "22") (name "Net-(D2-PF7_(ADC7{slash}TDI))") (class "Default")
      (node (ref "C2") (pin "2") (pinfunction "2_2") (pintype "passive"))
      (node (ref "D2") (pin "90") (pinfunction "PF7_(ADC7/TDI)_90") (pintype "bidirectional"))
      (node (ref "R26") (pin "2") (pinfunction "2_2") (pintype "passive"))
      (node (ref "R5") (pin "2") (pinfunction "2_2") (pintype "passive"))
    )
    (net (code "23") (name "Net-(D2-PH0_(RXD2))") (class "Default")
      (node (ref "D2") (pin "12") (pinfunction "PH0_(RXD2)_12") (pintype "bidirectional"))
      (node (ref "X1") (pin "2") (pinfunction "2_2") (pintype "passive"))
    )
    (net (code "24") (name "Net-(D2-PH1_(TXD2))") (class "Default")
      (node (ref "D2") (pin "13") (pinfunction "PH1_(TXD2)_13") (pintype "bidirectional"))
      (node (ref "X1") (pin "3") (pinfunction "3_3") (pintype "passive"))
    )
    (net (code "25") (name "Net-(D2-PK0_(ADC8{slash}PCINT16))") (class "Default")
      (node (ref "D2") (pin "89") (pinfunction "PK0_(ADC8/PCINT16)_89") (pintype "bidirectional"))
      (node (ref "R18") (pin "1") (pinfunction "1_1") (pintype "passive"))
      (node (ref "R21") (pin "2") (pinfunction "2_2") (pintype "passive"))
    )
    (net (code "26") (name "Net-(D2-PK1_(ADC9{slash}PCINT17))") (class "Default")
      (node (ref "C7") (pin "2") (pinfunction "2_2") (pintype "passive"))
      (node (ref "D2") (pin "88") (pinfunction "PK1_(ADC9/PCINT17)_88") (pintype "bidirectional"))
      (node (ref "R24") (pin "2") (pinfunction "2_2") (pintype "passive"))
      (node (ref "R7") (pin "2") (pinfunction "2_2") (pintype "passive"))
    )
    (net (code "27") (name "Net-(D2-PK2_(ADC10{slash}PCINT18))") (class "Default")
      (node (ref "C9") (pin "1") (pinfunction "1_1") (pintype "passive"))
      (node (ref "D2") (pin "87") (pinfunction "PK2_(ADC10/PCINT18)_87") (pintype "bidirectional"))
      (node (ref "R11") (pin "2") (pinfunction "2_2") (pintype "passive"))
      (node (ref "R30") (pin "2") (pinfunction "2_2") (pintype "passive"))
    )
    (net (code "28") (name "Net-(D2-PK3_(ADC11{slash}PCINT19))") (class "Default")
      (node (ref "C8") (pin "2") (pinfunction "2_2") (pintype "passive"))
      (node (ref "D2") (pin "86") (pinfunction "PK3_(ADC11/PCINT19)_86") (pintype "bidirectional"))
      (node (ref "R10") (pin "2") (pinfunction "2_2") (pintype "passive"))
      (node (ref "R31") (pin "2") (pinfunction "2_2") (pintype "passive"))
    )
    (net (code "29") (name "Net-(D2-PK4_(ADC12{slash}PCINT20))") (class "Default")
      (node (ref "C11") (pin "2") (pinfunction "2_2") (pintype "passive"))
      (node (ref "D2") (pin "85") (pinfunction "PK4_(ADC12/PCINT20)_85") (pintype "bidirectional"))
      (node (ref "R13") (pin "1") (pinfunction "1_1") (pintype "passive"))
      (node (ref "R32") (pin "1") (pinfunction "1_1") (pintype "passive"))
    )
    (net (code "30") (name "Net-(D2-PK5_(ADC13{slash}PCINT21))") (class "Default")
      (node (ref "C10") (pin "1") (pinfunction "1_1") (pintype "passive"))
      (node (ref "D2") (pin "84") (pinfunction "PK5_(ADC13/PCINT21)_84") (pintype "bidirectional"))
      (node (ref "R14") (pin "1") (pinfunction "1_1") (pintype "passive"))
      (node (ref "R33") (pin "1") (pinfunction "1_1") (pintype "passive"))
    )
    (net (code "31") (name "Net-(D2-PK6_(ADC14{slash}PCINT22))") (class "Default")
      (node (ref "C12") (pin "2") (pinfunction "2_2") (pintype "passive"))
      (node (ref "D2") (pin "83") (pinfunction "PK6_(ADC14/PCINT22)_83") (pintype "bidirectional"))
      (node (ref "R16") (pin "2") (pinfunction "2_2") (pintype "passive"))
      (node (ref "R34") (pin "2") (pinfunction "2_2") (pintype "passive"))
    )
    (net (code "32") (name "Net-(D2-PK7_(ADC15{slash}PCINT23))") (class "Default")
      (node (ref "C13") (pin "2") (pinfunction "2_2") (pintype "passive"))
      (node (ref "D2") (pin "82") (pinfunction "PK7_(ADC15/PCINT23)_82") (pintype "bidirectional"))
      (node (ref "R17") (pin "2") (pinfunction "2_2") (pintype "passive"))
      (node (ref "R35") (pin "2") (pinfunction "2_2") (pintype "passive"))
    )
    (net (code "33") (name "Net-(D2-XTAL1)") (class "Default")
      (node (ref "C18") (pin "1") (pinfunction "1_1") (pintype "passive"))
      (node (ref "D2") (pin "34") (pinfunction "XTAL1_34") (pintype "input"))
      (node (ref "V1") (pin "1") (pinfunction "OSC1_1") (pintype "passive"))
    )
    (net (code "34") (name "Net-(D2-XTAL2)") (class "Default")
      (node (ref "C19") (pin "2") (pinfunction "2_2") (pintype "passive"))
      (node (ref "D2") (pin "33") (pinfunction "XTAL2_33") (pintype "output"))
      (node (ref "V1") (pin "2") (pinfunction "OSC2_2") (pintype "passive"))
    )
    (net (code "35") (name "Net-(D2-~{RESET})") (class "Default")
      (node (ref "D2") (pin "30") (pinfunction "~{RESET}_30") (pintype "input"))
      (node (ref "D4") (pin "9") (pinfunction "~{RST}_9") (pintype "bidirectional"))
      (node (ref "X4") (pin "3") (pinfunction "3_3") (pintype "passive"))
    )
    (net (code "36") (name "Net-(D3-CANH)") (class "Default")
      (node (ref "D3") (pin "7") (pinfunction "CANH_7") (pintype "input"))
      (node (ref "R15") (pin "1") (pinfunction "1_1") (pintype "passive"))
    )
    (net (code "37") (name "Net-(D3-CANL)") (class "Default")
      (node (ref "D3") (pin "6") (pinfunction "CANL_6") (pintype "input"))
      (node (ref "X2") (pin "4") (pinfunction "4_4") (pintype "passive"))
    )
    (net (code "38") (name "Net-(D3-RXD)") (class "Default")
      (node (ref "D3") (pin "4") (pinfunction "RXD_4") (pintype "output"))
      (node (ref "D5") (pin "2") (pinfunction "RXCAN_2") (pintype "input"))
    )
    (net (code "39") (name "Net-(D3-TXD)") (class "Default")
      (node (ref "D3") (pin "1") (pinfunction "TXD_1") (pintype "input"))
      (node (ref "D5") (pin "1") (pinfunction "TXCAN_1") (pintype "output"))
    )
    (net (code "40") (name "Net-(D4-D+)") (class "Default")
      (node (ref "D4") (pin "3") (pinfunction "D+_3") (pintype "bidirectional"))
      (node (ref "X5") (pin "3") (pinfunction "D+_3") (pintype "bidirectional"))
    )
    (net (code "41") (name "Net-(D4-D-)") (class "Default")
      (node (ref "D4") (pin "4") (pinfunction "D-_4") (pintype "bidirectional"))
      (node (ref "X5") (pin "2") (pinfunction "D-_2") (pintype "bidirectional"))
    )
    (net (code "42") (name "Net-(D4-REGIN)") (class "Default")
      (node (ref "C15") (pin "1") (pinfunction "1_1") (pintype "passive"))
      (node (ref "D4") (pin "7") (pinfunction "REGIN_7") (pintype "power_in"))
      (node (ref "D4") (pin "8") (pinfunction "VBUS_8") (pintype "input"))
      (node (ref "X5") (pin "1") (pinfunction "VBUS_1") (pintype "power_in"))
    )
    (net (code "43") (name "Net-(D5-OSC1)") (class "Default")
      (node (ref "C20") (pin "2") (pinfunction "2_2") (pintype "passive"))
      (node (ref "D5") (pin "9") (pinfunction "OSC1_9") (pintype "input"))
      (node (ref "V2") (pin "1") (pinfunction "OSC1_1") (pintype "passive"))
    )
    (net (code "44") (name "Net-(D5-OSC2)") (class "Default")
      (node (ref "C21") (pin "2") (pinfunction "2_2") (pintype "passive"))
      (node (ref "D5") (pin "8") (pinfunction "OSC2_8") (pintype "output"))
      (node (ref "V2") (pin "2") (pinfunction "OSC2_2") (pintype "passive"))
    )
    (net (code "45") (name "Net-(D5-~{RESET})") (class "Default")
      (node (ref "D5") (pin "19") (pinfunction "~{RESET}_19") (pintype "input"))
      (node (ref "R20") (pin "2") (pinfunction "2_2") (pintype "passive"))
    )
    (net (code "46") (name "Net-(Q1-PadB1)") (class "Default")
      (node (ref "Q1") (pin "B1") (pinfunction "B1_B1") (pintype "passive"))
      (node (ref "Q1") (pin "B2") (pinfunction "B2_B2") (pintype "passive"))
      (node (ref "R1") (pin "1") (pinfunction "1_1") (pintype "passive"))
    )
    (net (code "47") (name "Net-(Q2-PadB1)") (class "Default")
      (node (ref "Q2") (pin "B1") (pinfunction "B1_B1") (pintype "passive"))
      (node (ref "Q2") (pin "B2") (pinfunction "B2_B2") (pintype "passive"))
      (node (ref "R2") (pin "1") (pinfunction "1_1") (pintype "passive"))
    )
    (net (code "48") (name "Net-(Q3-PadB1)") (class "Default")
      (node (ref "Q3") (pin "B1") (pinfunction "B1_B1") (pintype "passive"))
      (node (ref "Q3") (pin "B2") (pinfunction "B2_B2") (pintype "passive"))
      (node (ref "R3") (pin "1") (pinfunction "1_1") (pintype "passive"))
    )
    (net (code "49") (name "Net-(Q4-PadB1)") (class "Default")
      (node (ref "Q4") (pin "B1") (pinfunction "B1_B1") (pintype "passive"))
      (node (ref "Q4") (pin "B2") (pinfunction "B2_B2") (pintype "passive"))
      (node (ref "R6") (pin "1") (pinfunction "1_1") (pintype "passive"))
    )
    (net (code "50") (name "Net-(Q5-PadB1)") (class "Default")
      (node (ref "Q5") (pin "B1") (pinfunction "B1_B1") (pintype "passive"))
      (node (ref "Q5") (pin "B2") (pinfunction "B2_B2") (pintype "passive"))
      (node (ref "R4") (pin "1") (pinfunction "1_1") (pintype "passive"))
    )
    (net (code "51") (name "Net-(Q6-PadB1)") (class "Default")
      (node (ref "Q6") (pin "B1") (pinfunction "B1_B1") (pintype "passive"))
      (node (ref "Q6") (pin "B2") (pinfunction "B2_B2") (pintype "passive"))
      (node (ref "R5") (pin "1") (pinfunction "1_1") (pintype "passive"))
    )
    (net (code "52") (name "Net-(Q7-PadB1)") (class "Default")
      (node (ref "Q7") (pin "B1") (pinfunction "B1_B1") (pintype "passive"))
      (node (ref "Q7") (pin "B2") (pinfunction "B2_B2") (pintype "passive"))
      (node (ref "R7") (pin "1") (pinfunction "1_1") (pintype "passive"))
    )
    (net (code "53") (name "Net-(Q8-PadB1)") (class "Default")
      (node (ref "Q8") (pin "B1") (pinfunction "B1_B1") (pintype "passive"))
      (node (ref "Q8") (pin "B2") (pinfunction "B2_B2") (pintype "passive"))
      (node (ref "R10") (pin "1") (pinfunction "1_1") (pintype "passive"))
    )
    (net (code "54") (name "Net-(Q9-PadB1)") (class "Default")
      (node (ref "Q9") (pin "B1") (pinfunction "B1_B1") (pintype "passive"))
      (node (ref "Q9") (pin "B2") (pinfunction "B2_B2") (pintype "passive"))
      (node (ref "R11") (pin "1") (pinfunction "1_1") (pintype "passive"))
    )
    (net (code "55") (name "Net-(Q10-B)") (class "Default")
      (node (ref "Q10") (pin "2") (pinfunction "B_2") (pintype "passive"))
      (node (ref "R12") (pin "2") (pinfunction "2_2") (pintype "passive"))
    )
    (net (code "56") (name "Net-(Q10-E)") (class "Default")
      (node (ref "LS1") (pin "1") (pinfunction "1_1") (pintype "passive"))
      (node (ref "Q10") (pin "3") (pinfunction "E_3") (pintype "passive"))
    )
    (net (code "57") (name "Net-(Q11-PadB1)") (class "Default")
      (node (ref "Q11") (pin "B1") (pinfunction "B1_B1") (pintype "passive"))
      (node (ref "Q11") (pin "B2") (pinfunction "B2_B2") (pintype "passive"))
      (node (ref "R14") (pin "2") (pinfunction "2_2") (pintype "passive"))
    )
    (net (code "58") (name "Net-(Q12-PadB1)") (class "Default")
      (node (ref "Q12") (pin "B1") (pinfunction "B1_B1") (pintype "passive"))
      (node (ref "Q12") (pin "B2") (pinfunction "B2_B2") (pintype "passive"))
      (node (ref "R13") (pin "2") (pinfunction "2_2") (pintype "passive"))
    )
    (net (code "59") (name "Net-(Q13-PadB1)") (class "Default")
      (node (ref "Q13") (pin "B1") (pinfunction "B1_B1") (pintype "passive"))
      (node (ref "R17") (pin "1") (pinfunction "1_1") (pintype "passive"))
    )
    (net (code "60") (name "Net-(Q14-PadB1)") (class "Default")
      (node (ref "Q14") (pin "B1") (pinfunction "B1_B1") (pintype "passive"))
      (node (ref "Q14") (pin "B2") (pinfunction "B2_B2") (pintype "passive"))
      (node (ref "R16") (pin "1") (pinfunction "1_1") (pintype "passive"))
    )
    (net (code "61") (name "Net-(Q15-PadB1)") (class "Default")
      (node (ref "Q15") (pin "B1") (pinfunction "B1_B1") (pintype "passive"))
      (node (ref "Q15") (pin "B2") (pinfunction "B2_B2") (pintype "passive"))
      (node (ref "R19") (pin "2") (pinfunction "2_2") (pintype "passive"))
    )
    (net (code "62") (name "Net-(Q16-PadB1)") (class "Default")
      (node (ref "Q16") (pin "B1") (pinfunction "B1_B1") (pintype "passive"))
      (node (ref "Q16") (pin "B2") (pinfunction "B2_B2") (pintype "passive"))
      (node (ref "R22") (pin "2") (pinfunction "2_2") (pintype "passive"))
    )
    (net (code "63") (name "Net-(R15-Pad2)") (class "Default")
      (node (ref "R15") (pin "2") (pinfunction "2_2") (pintype "passive"))
      (node (ref "X2") (pin "3") (pinfunction "3_3") (pintype "passive"))
    )
    (net (code "64") (name "Net-(X5-GND)") (class "Default")
      (node (ref "C15") (pin "2") (pinfunction "2_2") (pintype "passive"))
      (node (ref "C16") (pin "2") (pinfunction "2_2") (pintype "passive"))
      (node (ref "X5") (pin "5") (pinfunction "GND_5") (pintype "power_in"))
    )
    (net (code "65") (name "unconnected-(D2-PA3_(AD3)-Pad75)") (class "Default")
      (node (ref "D2") (pin "75") (pinfunction "PA3_(AD3)_75") (pintype "bidirectional+no_connect"))
    )
    (net (code "66") (name "unconnected-(D2-PA4_(AD4)-Pad74)") (class "Default")
      (node (ref "D2") (pin "74") (pinfunction "PA4_(AD4)_74") (pintype "bidirectional+no_connect"))
    )
    (net (code "67") (name "unconnected-(D2-PA5_(AD5)-Pad73)") (class "Default")
      (node (ref "D2") (pin "73") (pinfunction "PA5_(AD5)_73") (pintype "bidirectional+no_connect"))
    )
    (net (code "68") (name "unconnected-(D2-PA6_(AD6)-Pad72)") (class "Default")
      (node (ref "D2") (pin "72") (pinfunction "PA6_(AD6)_72") (pintype "bidirectional+no_connect"))
    )
    (net (code "69") (name "unconnected-(D2-PA7_(AD7)-Pad71)") (class "Default")
      (node (ref "D2") (pin "71") (pinfunction "PA7_(AD7)_71") (pintype "bidirectional+no_connect"))
    )
    (net (code "70") (name "unconnected-(D2-PB4_(OC2A{slash}PCINT4)-Pad23)") (class "Default")
      (node (ref "D2") (pin "23") (pinfunction "PB4_(OC2A/PCINT4)_23") (pintype "bidirectional+no_connect"))
    )
    (net (code "71") (name "unconnected-(D2-PB5_(OC1A{slash}PCINT5)-Pad24)") (class "Default")
      (node (ref "D2") (pin "24") (pinfunction "PB5_(OC1A/PCINT5)_24") (pintype "bidirectional+no_connect"))
    )
    (net (code "72") (name "unconnected-(D2-PB6_(OC1B{slash}PCINT6)-Pad25)") (class "Default")
      (node (ref "D2") (pin "25") (pinfunction "PB6_(OC1B/PCINT6)_25") (pintype "bidirectional+no_connect"))
    )
    (net (code "73") (name "unconnected-(D2-PB7_(OC0A{slash}OC1C{slash}PCINT7)-Pad26)") (class "Default")
      (node (ref "D2") (pin "26") (pinfunction "PB7_(OC0A/OC1C/PCINT7)_26") (pintype "bidirectional+no_connect"))
    )
    (net (code "74") (name "unconnected-(D2-PC0_(A8)-Pad53)") (class "Default")
      (node (ref "D2") (pin "53") (pinfunction "PC0_(A8)_53") (pintype "bidirectional+no_connect"))
    )
    (net (code "75") (name "unconnected-(D2-PC1_(A9)-Pad54)") (class "Default")
      (node (ref "D2") (pin "54") (pinfunction "PC1_(A9)_54") (pintype "bidirectional+no_connect"))
    )
    (net (code "76") (name "unconnected-(D2-PC2_(A10)-Pad55)") (class "Default")
      (node (ref "D2") (pin "55") (pinfunction "PC2_(A10)_55") (pintype "bidirectional+no_connect"))
    )
    (net (code "77") (name "unconnected-(D2-PC3_(A11)-Pad56)") (class "Default")
      (node (ref "D2") (pin "56") (pinfunction "PC3_(A11)_56") (pintype "bidirectional+no_connect"))
    )
    (net (code "78") (name "unconnected-(D2-PC4_(A12)-Pad57)") (class "Default")
      (node (ref "D2") (pin "57") (pinfunction "PC4_(A12)_57") (pintype "bidirectional+no_connect"))
    )
    (net (code "79") (name "unconnected-(D2-PC5_(A13)-Pad58)") (class "Default")
      (node (ref "D2") (pin "58") (pinfunction "PC5_(A13)_58") (pintype "bidirectional+no_connect"))
    )
    (net (code "80") (name "unconnected-(D2-PC6_(A14)-Pad59)") (class "Default")
      (node (ref "D2") (pin "59") (pinfunction "PC6_(A14)_59") (pintype "bidirectional+no_connect"))
    )
    (net (code "81") (name "unconnected-(D2-PC7_(A15)-Pad60)") (class "Default")
      (node (ref "D2") (pin "60") (pinfunction "PC7_(A15)_60") (pintype "bidirectional+no_connect"))
    )
    (net (code "82") (name "unconnected-(D2-PD0_(SCL{slash}INT0)-Pad43)") (class "Default")
      (node (ref "D2") (pin "43") (pinfunction "PD0_(SCL/INT0)_43") (pintype "bidirectional+no_connect"))
    )
    (net (code "83") (name "unconnected-(D2-PD1_(SDA{slash}INT1)-Pad44)") (class "Default")
      (node (ref "D2") (pin "44") (pinfunction "PD1_(SDA/INT1)_44") (pintype "bidirectional+no_connect"))
    )
    (net (code "84") (name "unconnected-(D2-PD2_(RXD1{slash}INT2)-Pad45)") (class "Default")
      (node (ref "D2") (pin "45") (pinfunction "PD2_(RXD1/INT2)_45") (pintype "bidirectional+no_connect"))
    )
    (net (code "85") (name "unconnected-(D2-PD3_(TXD1{slash}INT3)-Pad46)") (class "Default")
      (node (ref "D2") (pin "46") (pinfunction "PD3_(TXD1/INT3)_46") (pintype "bidirectional+no_connect"))
    )
    (net (code "86") (name "unconnected-(D2-PD4_(ICP1)-Pad47)") (class "Default")
      (node (ref "D2") (pin "47") (pinfunction "PD4_(ICP1)_47") (pintype "bidirectional+no_connect"))
    )
    (net (code "87") (name "unconnected-(D2-PD5_(XCK1)-Pad48)") (class "Default")
      (node (ref "D2") (pin "48") (pinfunction "PD5_(XCK1)_48") (pintype "bidirectional+no_connect"))
    )
    (net (code "88") (name "unconnected-(D2-PD6_(T1)-Pad49)") (class "Default")
      (node (ref "D2") (pin "49") (pinfunction "PD6_(T1)_49") (pintype "bidirectional+no_connect"))
    )
    (net (code "89") (name "unconnected-(D2-PD7_(T0)-Pad50)") (class "Default")
      (node (ref "D2") (pin "50") (pinfunction "PD7_(T0)_50") (pintype "bidirectional+no_connect"))
    )
    (net (code "90") (name "unconnected-(D2-PE2_(XCK0{slash}AIN0)-Pad4)") (class "Default")
      (node (ref "D2") (pin "4") (pinfunction "PE2_(XCK0/AIN0)_4") (pintype "bidirectional+no_connect"))
    )
    (net (code "91") (name "unconnected-(D2-PE3_(OC3A{slash}AIN1)-Pad5)") (class "Default")
      (node (ref "D2") (pin "5") (pinfunction "PE3_(OC3A/AIN1)_5") (pintype "bidirectional+no_connect"))
    )
    (net (code "92") (name "unconnected-(D2-PE4_(OC3B{slash}INT4)-Pad6)") (class "Default")
      (node (ref "D2") (pin "6") (pinfunction "PE4_(OC3B/INT4)_6") (pintype "bidirectional+no_connect"))
    )
    (net (code "93") (name "unconnected-(D2-PE5_(OC3C{slash}INT5)-Pad7)") (class "Default")
      (node (ref "D2") (pin "7") (pinfunction "PE5_(OC3C/INT5)_7") (pintype "bidirectional+no_connect"))
    )
    (net (code "94") (name "unconnected-(D2-PE6_(T3{slash}INT6)-Pad8)") (class "Default")
      (node (ref "D2") (pin "8") (pinfunction "PE6_(T3/INT6)_8") (pintype "bidirectional+no_connect"))
    )
    (net (code "95") (name "unconnected-(D2-PE7_(CLKO{slash}ICP3{slash}INT7)-Pad9)") (class "Default")
      (node (ref "D2") (pin "9") (pinfunction "PE7_(CLKO/ICP3/INT7)_9") (pintype "bidirectional+no_connect"))
    )
    (net (code "96") (name "unconnected-(D2-PG0_(WR)-Pad51)") (class "Default")
      (node (ref "D2") (pin "51") (pinfunction "PG0_(WR)_51") (pintype "bidirectional+no_connect"))
    )
    (net (code "97") (name "unconnected-(D2-PG1_(RD)-Pad52)") (class "Default")
      (node (ref "D2") (pin "52") (pinfunction "PG1_(RD)_52") (pintype "bidirectional+no_connect"))
    )
    (net (code "98") (name "unconnected-(D2-PG2_(ALE)-Pad70)") (class "Default")
      (node (ref "D2") (pin "70") (pinfunction "PG2_(ALE)_70") (pintype "bidirectional+no_connect"))
    )
    (net (code "99") (name "unconnected-(D2-PG3_(TOSC2)-Pad28)") (class "Default")
      (node (ref "D2") (pin "28") (pinfunction "PG3_(TOSC2)_28") (pintype "bidirectional+no_connect"))
    )
    (net (code "100") (name "unconnected-(D2-PG4_(TOSC1)-Pad29)") (class "Default")
      (node (ref "D2") (pin "29") (pinfunction "PG4_(TOSC1)_29") (pintype "bidirectional+no_connect"))
    )
    (net (code "101") (name "unconnected-(D2-PG5_(OC0B)-Pad1)") (class "Default")
      (node (ref "D2") (pin "1") (pinfunction "PG5_(OC0B)_1") (pintype "bidirectional+no_connect"))
    )
    (net (code "102") (name "unconnected-(D2-PH2_(XCK2)-Pad14)") (class "Default")
      (node (ref "D2") (pin "14") (pinfunction "PH2_(XCK2)_14") (pintype "bidirectional+no_connect"))
    )
    (net (code "103") (name "unconnected-(D2-PH3_(OC4A)-Pad15)") (class "Default")
      (node (ref "D2") (pin "15") (pinfunction "PH3_(OC4A)_15") (pintype "bidirectional+no_connect"))
    )
    (net (code "104") (name "unconnected-(D2-PH4_(OC4B)-Pad16)") (class "Default")
      (node (ref "D2") (pin "16") (pinfunction "PH4_(OC4B)_16") (pintype "bidirectional+no_connect"))
    )
    (net (code "105") (name "unconnected-(D2-PH5_(OC4C)-Pad17)") (class "Default")
      (node (ref "D2") (pin "17") (pinfunction "PH5_(OC4C)_17") (pintype "bidirectional+no_connect"))
    )
    (net (code "106") (name "unconnected-(D2-PH6_(OC2B)-Pad18)") (class "Default")
      (node (ref "D2") (pin "18") (pinfunction "PH6_(OC2B)_18") (pintype "bidirectional+no_connect"))
    )
    (net (code "107") (name "unconnected-(D2-PH7_(T4)-Pad27)") (class "Default")
      (node (ref "D2") (pin "27") (pinfunction "PH7_(T4)_27") (pintype "bidirectional+no_connect"))
    )
    (net (code "108") (name "unconnected-(D2-PJ0_(RXD3{slash}PCINT9)-Pad63)") (class "Default")
      (node (ref "D2") (pin "63") (pinfunction "PJ0_(RXD3/PCINT9)_63") (pintype "bidirectional+no_connect"))
    )
    (net (code "109") (name "unconnected-(D2-PJ1_(TXD3{slash}PCINT10)-Pad64)") (class "Default")
      (node (ref "D2") (pin "64") (pinfunction "PJ1_(TXD3/PCINT10)_64") (pintype "bidirectional+no_connect"))
    )
    (net (code "110") (name "unconnected-(D2-PJ2_(XCK3{slash}PCINT11)-Pad65)") (class "Default")
      (node (ref "D2") (pin "65") (pinfunction "PJ2_(XCK3/PCINT11)_65") (pintype "bidirectional+no_connect"))
    )
    (net (code "111") (name "unconnected-(D2-PJ3_(PCINT12)-Pad66)") (class "Default")
      (node (ref "D2") (pin "66") (pinfunction "PJ3_(PCINT12)_66") (pintype "bidirectional+no_connect"))
    )
    (net (code "112") (name "unconnected-(D2-PJ4_(PCINT13)-Pad67)") (class "Default")
      (node (ref "D2") (pin "67") (pinfunction "PJ4_(PCINT13)_67") (pintype "bidirectional+no_connect"))
    )
    (net (code "113") (name "unconnected-(D2-PJ5_(PCINT14)-Pad68)") (class "Default")
      (node (ref "D2") (pin "68") (pinfunction "PJ5_(PCINT14)_68") (pintype "bidirectional+no_connect"))
    )
    (net (code "114") (name "unconnected-(D2-PJ6_(PCINT15)-Pad69)") (class "Default")
      (node (ref "D2") (pin "69") (pinfunction "PJ6_(PCINT15)_69") (pintype "bidirectional+no_connect"))
    )
    (net (code "115") (name "unconnected-(D2-PJ7-Pad79)") (class "Default")
      (node (ref "D2") (pin "79") (pinfunction "PJ7_79") (pintype "bidirectional+no_connect"))
    )
    (net (code "116") (name "unconnected-(D2-PL0_(ICP4)-Pad35)") (class "Default")
      (node (ref "D2") (pin "35") (pinfunction "PL0_(ICP4)_35") (pintype "bidirectional+no_connect"))
    )
    (net (code "117") (name "unconnected-(D2-PL1_(ICP5)-Pad36)") (class "Default")
      (node (ref "D2") (pin "36") (pinfunction "PL1_(ICP5)_36") (pintype "bidirectional+no_connect"))
    )
    (net (code "118") (name "unconnected-(D2-PL2_(T5)-Pad37)") (class "Default")
      (node (ref "D2") (pin "37") (pinfunction "PL2_(T5)_37") (pintype "bidirectional+no_connect"))
    )
    (net (code "119") (name "unconnected-(D2-PL3_(OC5A)-Pad38)") (class "Default")
      (node (ref "D2") (pin "38") (pinfunction "PL3_(OC5A)_38") (pintype "bidirectional+no_connect"))
    )
    (net (code "120") (name "unconnected-(D2-PL4_(OC5B)-Pad39)") (class "Default")
      (node (ref "D2") (pin "39") (pinfunction "PL4_(OC5B)_39") (pintype "bidirectional+no_connect"))
    )
    (net (code "121") (name "unconnected-(D2-PL5_(OC5C)-Pad40)") (class "Default")
      (node (ref "D2") (pin "40") (pinfunction "PL5_(OC5C)_40") (pintype "bidirectional+no_connect"))
    )
    (net (code "122") (name "unconnected-(D2-PL6-Pad41)") (class "Default")
      (node (ref "D2") (pin "41") (pinfunction "PL6_41") (pintype "bidirectional+no_connect"))
    )
    (net (code "123") (name "unconnected-(D2-PL7-Pad42)") (class "Default")
      (node (ref "D2") (pin "42") (pinfunction "PL7_42") (pintype "bidirectional+no_connect"))
    )
    (net (code "124") (name "unconnected-(D3-Vref-Pad5)") (class "Default")
      (node (ref "D3") (pin "5") (pinfunction "Vref_5") (pintype "power_in+no_connect"))
    )
    (net (code "125") (name "unconnected-(D4-GPIO.0-Pad19)") (class "Default")
      (node (ref "D4") (pin "19") (pinfunction "GPIO.0_19") (pintype "bidirectional+no_connect"))
    )
    (net (code "126") (name "unconnected-(D4-GPIO.1-Pad18)") (class "Default")
      (node (ref "D4") (pin "18") (pinfunction "GPIO.1_18") (pintype "bidirectional+no_connect"))
    )
    (net (code "127") (name "unconnected-(D4-GPIO.2-Pad17)") (class "Default")
      (node (ref "D4") (pin "17") (pinfunction "GPIO.2_17") (pintype "bidirectional+no_connect"))
    )
    (net (code "128") (name "unconnected-(D4-GPIO.3-Pad16)") (class "Default")
      (node (ref "D4") (pin "16") (pinfunction "GPIO.3_16") (pintype "bidirectional+no_connect"))
    )
    (net (code "129") (name "unconnected-(D4-NC-Pad10)") (class "Default")
      (node (ref "D4") (pin "10") (pinfunction "NC_10") (pintype "passive+no_connect"))
    )
    (net (code "130") (name "unconnected-(D4-NC-Pad13)") (class "Default")
      (node (ref "D4") (pin "13") (pinfunction "NC_13") (pintype "passive"))
    )
    (net (code "131") (name "unconnected-(D4-NC-Pad14)") (class "Default")
      (node (ref "D4") (pin "14") (pinfunction "NC_14") (pintype "passive+no_connect"))
    )
    (net (code "132") (name "unconnected-(D4-NC-Pad15)") (class "Default")
      (node (ref "D4") (pin "15") (pinfunction "NC_15") (pintype "passive+no_connect"))
    )
    (net (code "133") (name "unconnected-(D4-NC-Pad20)") (class "Default")
      (node (ref "D4") (pin "20") (pinfunction "NC_20") (pintype "passive+no_connect"))
    )
    (net (code "134") (name "unconnected-(D4-NC-Pad21)") (class "Default")
      (node (ref "D4") (pin "21") (pinfunction "NC_21") (pintype "passive+no_connect"))
    )
    (net (code "135") (name "unconnected-(D4-SUSPEND-Pad12)") (class "Default")
      (node (ref "D4") (pin "12") (pinfunction "SUSPEND_12") (pintype "output+no_connect"))
    )
    (net (code "136") (name "unconnected-(D4-~{CTS}-Pad22)") (class "Default")
      (node (ref "D4") (pin "22") (pinfunction "~{CTS}_22") (pintype "input+no_connect"))
    )
    (net (code "137") (name "unconnected-(D4-~{DCD}-Pad28)") (class "Default")
      (node (ref "D4") (pin "28") (pinfunction "~{DCD}_28") (pintype "input+no_connect"))
    )
    (net (code "138") (name "unconnected-(D4-~{DSR}-Pad26)") (class "Default")
      (node (ref "D4") (pin "26") (pinfunction "~{DSR}_26") (pintype "input+no_connect"))
    )
    (net (code "139") (name "unconnected-(D4-~{DTR}-Pad27)") (class "Default")
      (node (ref "D4") (pin "27") (pinfunction "~{DTR}_27") (pintype "output+no_connect"))
    )
    (net (code "140") (name "unconnected-(D4-~{RI}-Pad1)") (class "Default")
      (node (ref "D4") (pin "1") (pinfunction "~{RI}_1") (pintype "input+no_connect"))
    )
    (net (code "141") (name "unconnected-(D4-~{RTS}-Pad23)") (class "Default")
      (node (ref "D4") (pin "23") (pinfunction "~{RTS}_23") (pintype "output+no_connect"))
    )
    (net (code "142") (name "unconnected-(D4-~{SUSPEND}-Pad11)") (class "Default")
      (node (ref "D4") (pin "11") (pinfunction "~{SUSPEND}_11") (pintype "output+no_connect"))
    )
    (net (code "143") (name "unconnected-(D5-CLKOUT{slash}SOF-Pad3)") (class "Default")
      (node (ref "D5") (pin "3") (pinfunction "CLKOUT/SOF_3") (pintype "output+no_connect"))
    )
    (net (code "144") (name "unconnected-(D5-NC-Pad6)") (class "Default")
      (node (ref "D5") (pin "6") (pinfunction "NC_6") (pintype "passive+no_connect"))
    )
    (net (code "145") (name "unconnected-(D5-NC-Pad15)") (class "Default")
      (node (ref "D5") (pin "15") (pinfunction "NC_15") (pintype "passive+no_connect"))
    )
    (net (code "146") (name "unconnected-(D5-~{INT}-Pad13)") (class "Default")
      (node (ref "D5") (pin "13") (pinfunction "~{INT}_13") (pintype "output+no_connect"))
    )
    (net (code "147") (name "unconnected-(D5-~{RX0BF}-Pad12)") (class "Default")
      (node (ref "D5") (pin "12") (pinfunction "~{RX0BF}_12") (pintype "output+no_connect"))
    )
    (net (code "148") (name "unconnected-(D5-~{RX1BF}-Pad11)") (class "Default")
      (node (ref "D5") (pin "11") (pinfunction "~{RX1BF}_11") (pintype "output+no_connect"))
    )
    (net (code "149") (name "unconnected-(D5-~{TX0RTS}-Pad4)") (class "Default")
      (node (ref "D5") (pin "4") (pinfunction "~{TX0RTS}_4") (pintype "input+no_connect"))
    )
    (net (code "150") (name "unconnected-(D5-~{TX1RTS}-Pad5)") (class "Default")
      (node (ref "D5") (pin "5") (pinfunction "~{TX1RTS}_5") (pintype "input+no_connect"))
    )
    (net (code "151") (name "unconnected-(D5-~{TX2RTS}-Pad7)") (class "Default")
      (node (ref "D5") (pin "7") (pinfunction "~{TX2RTS}_7") (pintype "input+no_connect"))
    )
    (net (code "152") (name "unconnected-(Q13-PadB2)") (class "Default")
      (node (ref "Q13") (pin "B2") (pinfunction "B2_B2") (pintype "passive"))
    )
    (net (code "153") (name "unconnected-(X3-NC-Pad2)") (class "Default")
      (node (ref "X3") (pin "2") (pinfunction "NC_2") (pintype "power_in+no_connect"))
    )
    (net (code "154") (name "unconnected-(X3-NC-Pad4)") (class "Default")
      (node (ref "X3") (pin "4") (pinfunction "NC_4") (pintype "power_in+no_connect"))
    )
    (net (code "155") (name "unconnected-(X3-OUT_1_1-Pad6)") (class "Default")
      (node (ref "X3") (pin "6") (pinfunction "OUT_1_1_6") (pintype "output+no_connect"))
    )
    (net (code "156") (name "unconnected-(X3-OUT_2_1-Pad8)") (class "Default")
      (node (ref "X3") (pin "8") (pinfunction "OUT_2_1_8") (pintype "output+no_connect"))
    )
    (net (code "157") (name "unconnected-(X5-ID-Pad4)") (class "Default")
      (node (ref "X5") (pin "4") (pinfunction "ID_4") (pintype "passive+no_connect"))
    )
    (net (code "158") (name "unconnected-(X5-MP1-Pad6)") (class "Default")
      (node (ref "X5") (pin "6") (pinfunction "MP1_6") (pintype "passive+no_connect"))
    )
    (net (code "159") (name "unconnected-(X5-MP2-Pad7)") (class "Default")
      (node (ref "X5") (pin "7") (pinfunction "MP2_7") (pintype "passive+no_connect"))
    )
    (net (code "160") (name "unconnected-(X5-MP3-Pad8)") (class "Default")
      (node (ref "X5") (pin "8") (pinfunction "MP3_8") (pintype "passive+no_connect"))
    )
    (net (code "161") (name "unconnected-(X5-MP4-Pad9)") (class "Default")
      (node (ref "X5") (pin "9") (pinfunction "MP4_9") (pintype "passive+no_connect"))
    )
  )
)
